# mcu.net
KiCad netlist of a schematic drawn in EAGLE
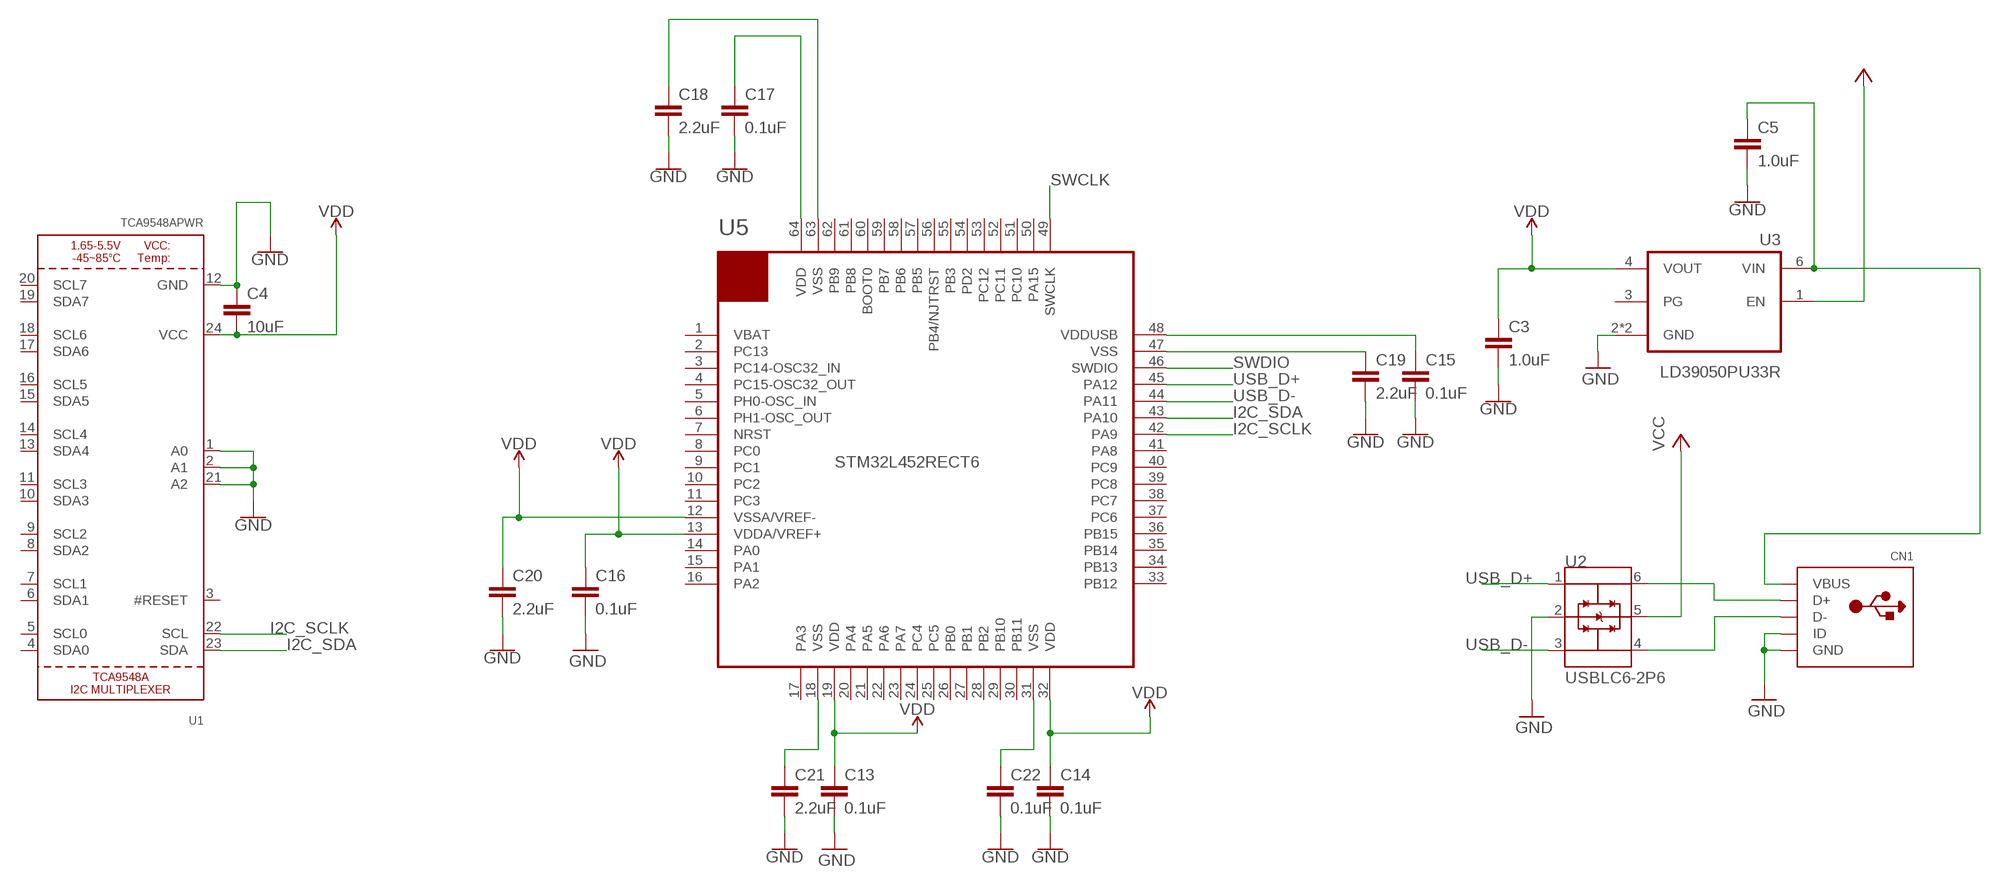
[diagram p0: schematic, sheet 1]

(export (version "E")
  (design (tool "Eeschema 10.0.6"))
  (components
    (comp (ref "C3")
      (value "1.0uF")
      (footprint "eagle-import:0402")
      (libsource (lib "eagle-import") (part "1.0UF-0402-16V-10%"))
    )
    (comp (ref "C4")
      (value "10uF")
      (footprint "eagle-import:0603")
      (libsource (lib "eagle-import") (part "10UF-0603-6.3V-20%"))
    )
    (comp (ref "C5")
      (value "1.0uF")
      (footprint "eagle-import:0402")
      (libsource (lib "eagle-import") (part "1.0UF-0402-16V-10%"))
    )
    (comp (ref "C13")
      (value "0.1uF")
      (footprint "eagle-import:0402-CAP")
      (libsource (lib "eagle-import") (part ".1UF-CER"))
    )
    (comp (ref "C14")
      (value "0.1uF")
      (footprint "eagle-import:0402-CAP")
      (libsource (lib "eagle-import") (part ".1UF-CER"))
    )
    (comp (ref "C15")
      (value "0.1uF")
      (footprint "eagle-import:0402-CAP")
      (libsource (lib "eagle-import") (part ".1UF-CER"))
    )
    (comp (ref "C16")
      (value "0.1uF")
      (footprint "eagle-import:0402-CAP")
      (libsource (lib "eagle-import") (part ".1UF-CER"))
    )
    (comp (ref "C17")
      (value "0.1uF")
      (footprint "eagle-import:0402-CAP")
      (libsource (lib "eagle-import") (part ".1UF-CER"))
    )
    (comp (ref "C18")
      (value "2.2uF")
      (footprint "eagle-import:0402-TIGHT")
      (libsource (lib "eagle-import") (part "2.2UF-0402_TIGHT-10V-10%-X5R"))
    )
    (comp (ref "C19")
      (value "2.2uF")
      (footprint "eagle-import:0402-TIGHT")
      (libsource (lib "eagle-import") (part "2.2UF-0402_TIGHT-10V-10%-X5R"))
    )
    (comp (ref "C20")
      (value "2.2uF")
      (footprint "eagle-import:0402-TIGHT")
      (libsource (lib "eagle-import") (part "2.2UF-0402_TIGHT-10V-10%-X5R"))
    )
    (comp (ref "C21")
      (value "2.2uF")
      (footprint "eagle-import:0402-TIGHT")
      (libsource (lib "eagle-import") (part "2.2UF-0402_TIGHT-10V-10%-X5R"))
    )
    (comp (ref "C22")
      (value "0.1uF")
      (footprint "eagle-import:0402-CAP")
      (libsource (lib "eagle-import") (part ".1UF-CER"))
    )
    (comp (ref "CN1")
      (value "USBMINIB")
      (footprint "eagle-import:USB-MINIB")
      (libsource (lib "eagle-import") (part "USBMINIB"))
    )
    (comp (ref "U1")
      (value "TCA9548APWR")
      (footprint "eagle-import:TSSOP24")
      (libsource (lib "eagle-import") (part "TCA9548A"))
    )
    (comp (ref "U2")
      (value "USBLC6-2P6")
      (footprint "eagle-import:SOT50P160X60-6N")
      (fields (field (name "MF") "STMicroelectronics"))
      (libsource (lib "eagle-import") (part "USBLC6-2P6"))
    )
    (comp (ref "U3")
      (value "LD39050PU33R")
      (footprint "eagle-import:SON95P300X300X100-7N")
      (fields (field (name "MF") "STMicroelectronics"))
      (libsource (lib "eagle-import") (part "LD39050PU33R"))
    )
    (comp (ref "U5")
      (value "STM32L452RECT6")
      (footprint "eagle-import:LQFP-64")
      (libsource (lib "eagle-import") (part "STM32L452RET6C"))
    )
  )
  (nets
    (net (code "1") (name "/I2C_SCLK") (class "Default")
      (node (ref "U1") (pin "22") (pinfunction "SCL_22") (pintype "bidirectional"))
      (node (ref "U5") (pin "42") (pinfunction "PA9_42") (pintype "bidirectional"))
    )
    (net (code "2") (name "/I2C_SDA") (class "Default")
      (node (ref "U1") (pin "23") (pinfunction "SDA_23") (pintype "bidirectional"))
      (node (ref "U5") (pin "43") (pinfunction "PA10_43") (pintype "bidirectional"))
    )
    (net (code "3") (name "/SWCLK") (class "Default")
      (node (ref "U5") (pin "49") (pinfunction "SWCLK_49") (pintype "bidirectional"))
    )
    (net (code "4") (name "/SWDIO") (class "Default")
      (node (ref "U5") (pin "46") (pinfunction "SWDIO_46") (pintype "bidirectional"))
    )
    (net (code "5") (name "/USB_D+") (class "Default")
      (node (ref "U2") (pin "1") (pinfunction "I/O1_1_1") (pintype "bidirectional"))
      (node (ref "U5") (pin "45") (pinfunction "PA12_45") (pintype "bidirectional"))
    )
    (net (code "6") (name "/USB_D-") (class "Default")
      (node (ref "U2") (pin "3") (pinfunction "I/O2_1_3") (pintype "bidirectional"))
      (node (ref "U5") (pin "44") (pinfunction "PA11_44") (pintype "bidirectional"))
    )
    (net (code "7") (name "/VBAT") (class "Default")
      (node (ref "U5") (pin "1") (pinfunction "VBAT_1") (pintype "power_in"))
    )
    (net (code "8") (name "GND") (class "Default")
      (node (ref "C13") (pin "2") (pinfunction "2_2") (pintype "passive"))
      (node (ref "C14") (pin "2") (pinfunction "2_2") (pintype "passive"))
      (node (ref "C15") (pin "2") (pinfunction "2_2") (pintype "passive"))
      (node (ref "C16") (pin "2") (pinfunction "2_2") (pintype "passive"))
      (node (ref "C17") (pin "2") (pinfunction "2_2") (pintype "passive"))
      (node (ref "C18") (pin "2") (pinfunction "2_2") (pintype "passive"))
      (node (ref "C19") (pin "2") (pinfunction "2_2") (pintype "passive"))
      (node (ref "C20") (pin "2") (pinfunction "2_2") (pintype "passive"))
      (node (ref "C21") (pin "2") (pinfunction "2_2") (pintype "passive"))
      (node (ref "C22") (pin "2") (pinfunction "2_2") (pintype "passive"))
      (node (ref "C3") (pin "2") (pinfunction "2_2") (pintype "passive"))
      (node (ref "C4") (pin "1") (pinfunction "1_1") (pintype "passive"))
      (node (ref "C5") (pin "2") (pinfunction "2_2") (pintype "passive"))
      (node (ref "CN1") (pin "GND") (pinfunction "GND_GND") (pintype "power_in"))
      (node (ref "CN1") (pin "ID") (pinfunction "ID_ID") (pintype "bidirectional"))
      (node (ref "U1") (pin "1") (pinfunction "A0_1") (pintype "bidirectional"))
      (node (ref "U1") (pin "12") (pinfunction "GND_12") (pintype "bidirectional"))
      (node (ref "U1") (pin "2") (pinfunction "A1_2") (pintype "bidirectional"))
      (node (ref "U1") (pin "21") (pinfunction "A2_21") (pintype "bidirectional"))
      (node (ref "U2") (pin "2") (pinfunction "GND_2") (pintype "power_in"))
      (node (ref "U3") (pin "2") (pinfunction "GND_2") (pintype "power_in"))
      (node (ref "U3") (pin "7") (pinfunction "GND_7") (pintype "power_in"))
    )
    (net (code "9") (name "Net-(C17-Pad1)") (class "Default")
      (node (ref "C17") (pin "1") (pinfunction "1_1") (pintype "passive"))
      (node (ref "U5") (pin "64") (pinfunction "VDD_64") (pintype "power_in"))
    )
    (net (code "10") (name "Net-(C18-Pad1)") (class "Default")
      (node (ref "C18") (pin "1") (pinfunction "1_1") (pintype "passive"))
      (node (ref "U5") (pin "63") (pinfunction "VSS_63") (pintype "power_in"))
    )
    (net (code "11") (name "Net-(C19-Pad1)") (class "Default")
      (node (ref "C19") (pin "1") (pinfunction "1_1") (pintype "passive"))
      (node (ref "U5") (pin "47") (pinfunction "VSS_47") (pintype "power_in"))
    )
    (net (code "12") (name "Net-(C21-Pad1)") (class "Default")
      (node (ref "C21") (pin "1") (pinfunction "1_1") (pintype "passive"))
      (node (ref "U5") (pin "18") (pinfunction "VSS_18") (pintype "power_in"))
    )
    (net (code "13") (name "Net-(C22-Pad1)") (class "Default")
      (node (ref "C22") (pin "1") (pinfunction "1_1") (pintype "passive"))
      (node (ref "U5") (pin "31") (pinfunction "VSS_31") (pintype "power_in"))
    )
    (net (code "14") (name "Net-(U2-I{slash}O1_2)") (class "Default")
      (node (ref "CN1") (pin "D+") (pinfunction "D+_D+") (pintype "bidirectional"))
      (node (ref "U2") (pin "6") (pinfunction "I/O1_2_6") (pintype "bidirectional"))
    )
    (net (code "15") (name "Net-(U2-I{slash}O2_2)") (class "Default")
      (node (ref "CN1") (pin "D-") (pinfunction "D-_D-") (pintype "bidirectional"))
      (node (ref "U2") (pin "4") (pinfunction "I/O2_2_4") (pintype "bidirectional"))
    )
    (net (code "16") (name "Net-(U3-VIN)") (class "Default")
      (node (ref "C5") (pin "1") (pinfunction "1_1") (pintype "passive"))
      (node (ref "CN1") (pin "VBUS") (pinfunction "VBUS_VBUS") (pintype "power_in"))
      (node (ref "U3") (pin "6") (pinfunction "VIN_6") (pintype "power_in"))
    )
    (net (code "17") (name "Net-(U5-VDDUSB)") (class "Default")
      (node (ref "C15") (pin "1") (pinfunction "1_1") (pintype "passive"))
      (node (ref "U5") (pin "48") (pinfunction "VDDUSB_48") (pintype "power_in"))
    )
    (net (code "18") (name "VCC") (class "Default")
      (node (ref "U2") (pin "5") (pinfunction "VBUS_5") (pintype "power_in"))
      (node (ref "U3") (pin "1") (pinfunction "EN_1") (pintype "input"))
    )
    (net (code "19") (name "VDD") (class "Default")
      (node (ref "C13") (pin "1") (pinfunction "1_1") (pintype "passive"))
      (node (ref "C14") (pin "1") (pinfunction "1_1") (pintype "passive"))
      (node (ref "C16") (pin "1") (pinfunction "1_1") (pintype "passive"))
      (node (ref "C20") (pin "1") (pinfunction "1_1") (pintype "passive"))
      (node (ref "C3") (pin "1") (pinfunction "1_1") (pintype "passive"))
      (node (ref "C4") (pin "2") (pinfunction "2_2") (pintype "passive"))
      (node (ref "U1") (pin "24") (pinfunction "VCC_24") (pintype "bidirectional"))
      (node (ref "U3") (pin "4") (pinfunction "VOUT_4") (pintype "output"))
      (node (ref "U5") (pin "12") (pinfunction "VSSA/VREF-_12") (pintype "power_in"))
      (node (ref "U5") (pin "13") (pinfunction "VDDA/VREF+_13") (pintype "power_in"))
      (node (ref "U5") (pin "19") (pinfunction "VDD_19") (pintype "power_in"))
      (node (ref "U5") (pin "32") (pinfunction "VDD_32") (pintype "power_in"))
    )
    (net (code "20") (name "unconnected-(U1-#RESET-Pad3)") (class "Default")
      (node (ref "U1") (pin "3") (pinfunction "#RESET_3") (pintype "bidirectional"))
    )
    (net (code "21") (name "unconnected-(U1-SCL0-Pad5)") (class "Default")
      (node (ref "U1") (pin "5") (pinfunction "SCL0_5") (pintype "bidirectional"))
    )
    (net (code "22") (name "unconnected-(U1-SCL1-Pad7)") (class "Default")
      (node (ref "U1") (pin "7") (pinfunction "SCL1_7") (pintype "bidirectional"))
    )
    (net (code "23") (name "unconnected-(U1-SCL2-Pad9)") (class "Default")
      (node (ref "U1") (pin "9") (pinfunction "SCL2_9") (pintype "bidirectional"))
    )
    (net (code "24") (name "unconnected-(U1-SCL3-Pad11)") (class "Default")
      (node (ref "U1") (pin "11") (pinfunction "SCL3_11") (pintype "bidirectional"))
    )
    (net (code "25") (name "unconnected-(U1-SCL4-Pad14)") (class "Default")
      (node (ref "U1") (pin "14") (pinfunction "SCL4_14") (pintype "bidirectional"))
    )
    (net (code "26") (name "unconnected-(U1-SCL5-Pad16)") (class "Default")
      (node (ref "U1") (pin "16") (pinfunction "SCL5_16") (pintype "bidirectional"))
    )
    (net (code "27") (name "unconnected-(U1-SCL6-Pad18)") (class "Default")
      (node (ref "U1") (pin "18") (pinfunction "SCL6_18") (pintype "bidirectional"))
    )
    (net (code "28") (name "unconnected-(U1-SCL7-Pad20)") (class "Default")
      (node (ref "U1") (pin "20") (pinfunction "SCL7_20") (pintype "bidirectional"))
    )
    (net (code "29") (name "unconnected-(U1-SDA0-Pad4)") (class "Default")
      (node (ref "U1") (pin "4") (pinfunction "SDA0_4") (pintype "bidirectional"))
    )
    (net (code "30") (name "unconnected-(U1-SDA1-Pad6)") (class "Default")
      (node (ref "U1") (pin "6") (pinfunction "SDA1_6") (pintype "bidirectional"))
    )
    (net (code "31") (name "unconnected-(U1-SDA2-Pad8)") (class "Default")
      (node (ref "U1") (pin "8") (pinfunction "SDA2_8") (pintype "bidirectional"))
    )
    (net (code "32") (name "unconnected-(U1-SDA3-Pad10)") (class "Default")
      (node (ref "U1") (pin "10") (pinfunction "SDA3_10") (pintype "bidirectional"))
    )
    (net (code "33") (name "unconnected-(U1-SDA4-Pad13)") (class "Default")
      (node (ref "U1") (pin "13") (pinfunction "SDA4_13") (pintype "bidirectional"))
    )
    (net (code "34") (name "unconnected-(U1-SDA5-Pad15)") (class "Default")
      (node (ref "U1") (pin "15") (pinfunction "SDA5_15") (pintype "bidirectional"))
    )
    (net (code "35") (name "unconnected-(U1-SDA6-Pad17)") (class "Default")
      (node (ref "U1") (pin "17") (pinfunction "SDA6_17") (pintype "bidirectional"))
    )
    (net (code "36") (name "unconnected-(U1-SDA7-Pad19)") (class "Default")
      (node (ref "U1") (pin "19") (pinfunction "SDA7_19") (pintype "bidirectional"))
    )
    (net (code "37") (name "unconnected-(U3-PG-Pad3)") (class "Default")
      (node (ref "U3") (pin "3") (pinfunction "PG_3") (pintype "bidirectional"))
    )
    (net (code "38") (name "unconnected-(U5-BOOT0-Pad60)") (class "Default")
      (node (ref "U5") (pin "60") (pinfunction "BOOT0_60") (pintype "input"))
    )
    (net (code "39") (name "unconnected-(U5-NRST-Pad7)") (class "Default")
      (node (ref "U5") (pin "7") (pinfunction "NRST_7") (pintype "bidirectional"))
    )
    (net (code "40") (name "unconnected-(U5-PA0-Pad14)") (class "Default")
      (node (ref "U5") (pin "14") (pinfunction "PA0_14") (pintype "bidirectional"))
    )
    (net (code "41") (name "unconnected-(U5-PA1-Pad15)") (class "Default")
      (node (ref "U5") (pin "15") (pinfunction "PA1_15") (pintype "bidirectional"))
    )
    (net (code "42") (name "unconnected-(U5-PA2-Pad16)") (class "Default")
      (node (ref "U5") (pin "16") (pinfunction "PA2_16") (pintype "bidirectional"))
    )
    (net (code "43") (name "unconnected-(U5-PA3-Pad17)") (class "Default")
      (node (ref "U5") (pin "17") (pinfunction "PA3_17") (pintype "bidirectional"))
    )
    (net (code "44") (name "unconnected-(U5-PA4-Pad20)") (class "Default")
      (node (ref "U5") (pin "20") (pinfunction "PA4_20") (pintype "bidirectional"))
    )
    (net (code "45") (name "unconnected-(U5-PA5-Pad21)") (class "Default")
      (node (ref "U5") (pin "21") (pinfunction "PA5_21") (pintype "bidirectional"))
    )
    (net (code "46") (name "unconnected-(U5-PA6-Pad22)") (class "Default")
      (node (ref "U5") (pin "22") (pinfunction "PA6_22") (pintype "bidirectional"))
    )
    (net (code "47") (name "unconnected-(U5-PA7-Pad23)") (class "Default")
      (node (ref "U5") (pin "23") (pinfunction "PA7_23") (pintype "bidirectional"))
    )
    (net (code "48") (name "unconnected-(U5-PA8-Pad41)") (class "Default")
      (node (ref "U5") (pin "41") (pinfunction "PA8_41") (pintype "bidirectional"))
    )
    (net (code "49") (name "unconnected-(U5-PA15-Pad50)") (class "Default")
      (node (ref "U5") (pin "50") (pinfunction "PA15_50") (pintype "bidirectional"))
    )
    (net (code "50") (name "unconnected-(U5-PB0-Pad26)") (class "Default")
      (node (ref "U5") (pin "26") (pinfunction "PB0_26") (pintype "bidirectional"))
    )
    (net (code "51") (name "unconnected-(U5-PB1-Pad27)") (class "Default")
      (node (ref "U5") (pin "27") (pinfunction "PB1_27") (pintype "bidirectional"))
    )
    (net (code "52") (name "unconnected-(U5-PB2-Pad28)") (class "Default")
      (node (ref "U5") (pin "28") (pinfunction "PB2_28") (pintype "bidirectional"))
    )
    (net (code "53") (name "unconnected-(U5-PB3-Pad55)") (class "Default")
      (node (ref "U5") (pin "55") (pinfunction "PB3_55") (pintype "bidirectional"))
    )
    (net (code "54") (name "unconnected-(U5-PB4{slash}NJTRST-Pad56)") (class "Default")
      (node (ref "U5") (pin "56") (pinfunction "PB4/NJTRST_56") (pintype "bidirectional"))
    )
    (net (code "55") (name "unconnected-(U5-PB5-Pad57)") (class "Default")
      (node (ref "U5") (pin "57") (pinfunction "PB5_57") (pintype "bidirectional"))
    )
    (net (code "56") (name "unconnected-(U5-PB6-Pad58)") (class "Default")
      (node (ref "U5") (pin "58") (pinfunction "PB6_58") (pintype "bidirectional"))
    )
    (net (code "57") (name "unconnected-(U5-PB7-Pad59)") (class "Default")
      (node (ref "U5") (pin "59") (pinfunction "PB7_59") (pintype "bidirectional"))
    )
    (net (code "58") (name "unconnected-(U5-PB8-Pad61)") (class "Default")
      (node (ref "U5") (pin "61") (pinfunction "PB8_61") (pintype "bidirectional"))
    )
    (net (code "59") (name "unconnected-(U5-PB9-Pad62)") (class "Default")
      (node (ref "U5") (pin "62") (pinfunction "PB9_62") (pintype "bidirectional"))
    )
    (net (code "60") (name "unconnected-(U5-PB10-Pad29)") (class "Default")
      (node (ref "U5") (pin "29") (pinfunction "PB10_29") (pintype "bidirectional"))
    )
    (net (code "61") (name "unconnected-(U5-PB11-Pad30)") (class "Default")
      (node (ref "U5") (pin "30") (pinfunction "PB11_30") (pintype "bidirectional"))
    )
    (net (code "62") (name "unconnected-(U5-PB12-Pad33)") (class "Default")
      (node (ref "U5") (pin "33") (pinfunction "PB12_33") (pintype "bidirectional"))
    )
    (net (code "63") (name "unconnected-(U5-PB13-Pad34)") (class "Default")
      (node (ref "U5") (pin "34") (pinfunction "PB13_34") (pintype "bidirectional"))
    )
    (net (code "64") (name "unconnected-(U5-PB14-Pad35)") (class "Default")
      (node (ref "U5") (pin "35") (pinfunction "PB14_35") (pintype "bidirectional"))
    )
    (net (code "65") (name "unconnected-(U5-PB15-Pad36)") (class "Default")
      (node (ref "U5") (pin "36") (pinfunction "PB15_36") (pintype "bidirectional"))
    )
    (net (code "66") (name "unconnected-(U5-PC0-Pad8)") (class "Default")
      (node (ref "U5") (pin "8") (pinfunction "PC0_8") (pintype "bidirectional"))
    )
    (net (code "67") (name "unconnected-(U5-PC1-Pad9)") (class "Default")
      (node (ref "U5") (pin "9") (pinfunction "PC1_9") (pintype "bidirectional"))
    )
    (net (code "68") (name "unconnected-(U5-PC2-Pad10)") (class "Default")
      (node (ref "U5") (pin "10") (pinfunction "PC2_10") (pintype "bidirectional"))
    )
    (net (code "69") (name "unconnected-(U5-PC3-Pad11)") (class "Default")
      (node (ref "U5") (pin "11") (pinfunction "PC3_11") (pintype "bidirectional"))
    )
    (net (code "70") (name "unconnected-(U5-PC4-Pad24)") (class "Default")
      (node (ref "U5") (pin "24") (pinfunction "PC4_24") (pintype "bidirectional"))
    )
    (net (code "71") (name "unconnected-(U5-PC5-Pad25)") (class "Default")
      (node (ref "U5") (pin "25") (pinfunction "PC5_25") (pintype "bidirectional"))
    )
    (net (code "72") (name "unconnected-(U5-PC6-Pad37)") (class "Default")
      (node (ref "U5") (pin "37") (pinfunction "PC6_37") (pintype "bidirectional"))
    )
    (net (code "73") (name "unconnected-(U5-PC7-Pad38)") (class "Default")
      (node (ref "U5") (pin "38") (pinfunction "PC7_38") (pintype "bidirectional"))
    )
    (net (code "74") (name "unconnected-(U5-PC8-Pad39)") (class "Default")
      (node (ref "U5") (pin "39") (pinfunction "PC8_39") (pintype "bidirectional"))
    )
    (net (code "75") (name "unconnected-(U5-PC9-Pad40)") (class "Default")
      (node (ref "U5") (pin "40") (pinfunction "PC9_40") (pintype "bidirectional"))
    )
    (net (code "76") (name "unconnected-(U5-PC10-Pad51)") (class "Default")
      (node (ref "U5") (pin "51") (pinfunction "PC10_51") (pintype "bidirectional"))
    )
    (net (code "77") (name "unconnected-(U5-PC11-Pad52)") (class "Default")
      (node (ref "U5") (pin "52") (pinfunction "PC11_52") (pintype "bidirectional"))
    )
    (net (code "78") (name "unconnected-(U5-PC12-Pad53)") (class "Default")
      (node (ref "U5") (pin "53") (pinfunction "PC12_53") (pintype "bidirectional"))
    )
    (net (code "79") (name "unconnected-(U5-PC13-Pad2)") (class "Default")
      (node (ref "U5") (pin "2") (pinfunction "PC13_2") (pintype "bidirectional"))
    )
    (net (code "80") (name "unconnected-(U5-PC14-OSC32_IN-Pad3)") (class "Default")
      (node (ref "U5") (pin "3") (pinfunction "PC14-OSC32_IN_3") (pintype "bidirectional"))
    )
    (net (code "81") (name "unconnected-(U5-PC15-OSC32_OUT-Pad4)") (class "Default")
      (node (ref "U5") (pin "4") (pinfunction "PC15-OSC32_OUT_4") (pintype "bidirectional"))
    )
    (net (code "82") (name "unconnected-(U5-PD2-Pad54)") (class "Default")
      (node (ref "U5") (pin "54") (pinfunction "PD2_54") (pintype "bidirectional"))
    )
    (net (code "83") (name "unconnected-(U5-PH0-OSC_IN-Pad5)") (class "Default")
      (node (ref "U5") (pin "5") (pinfunction "PH0-OSC_IN_5") (pintype "bidirectional"))
    )
    (net (code "84") (name "unconnected-(U5-PH1-OSC_OUT-Pad6)") (class "Default")
      (node (ref "U5") (pin "6") (pinfunction "PH1-OSC_OUT_6") (pintype "bidirectional"))
    )
  )
)
